# Power_Supply.net
KiCad netlist of a schematic drawn in Altium Designer
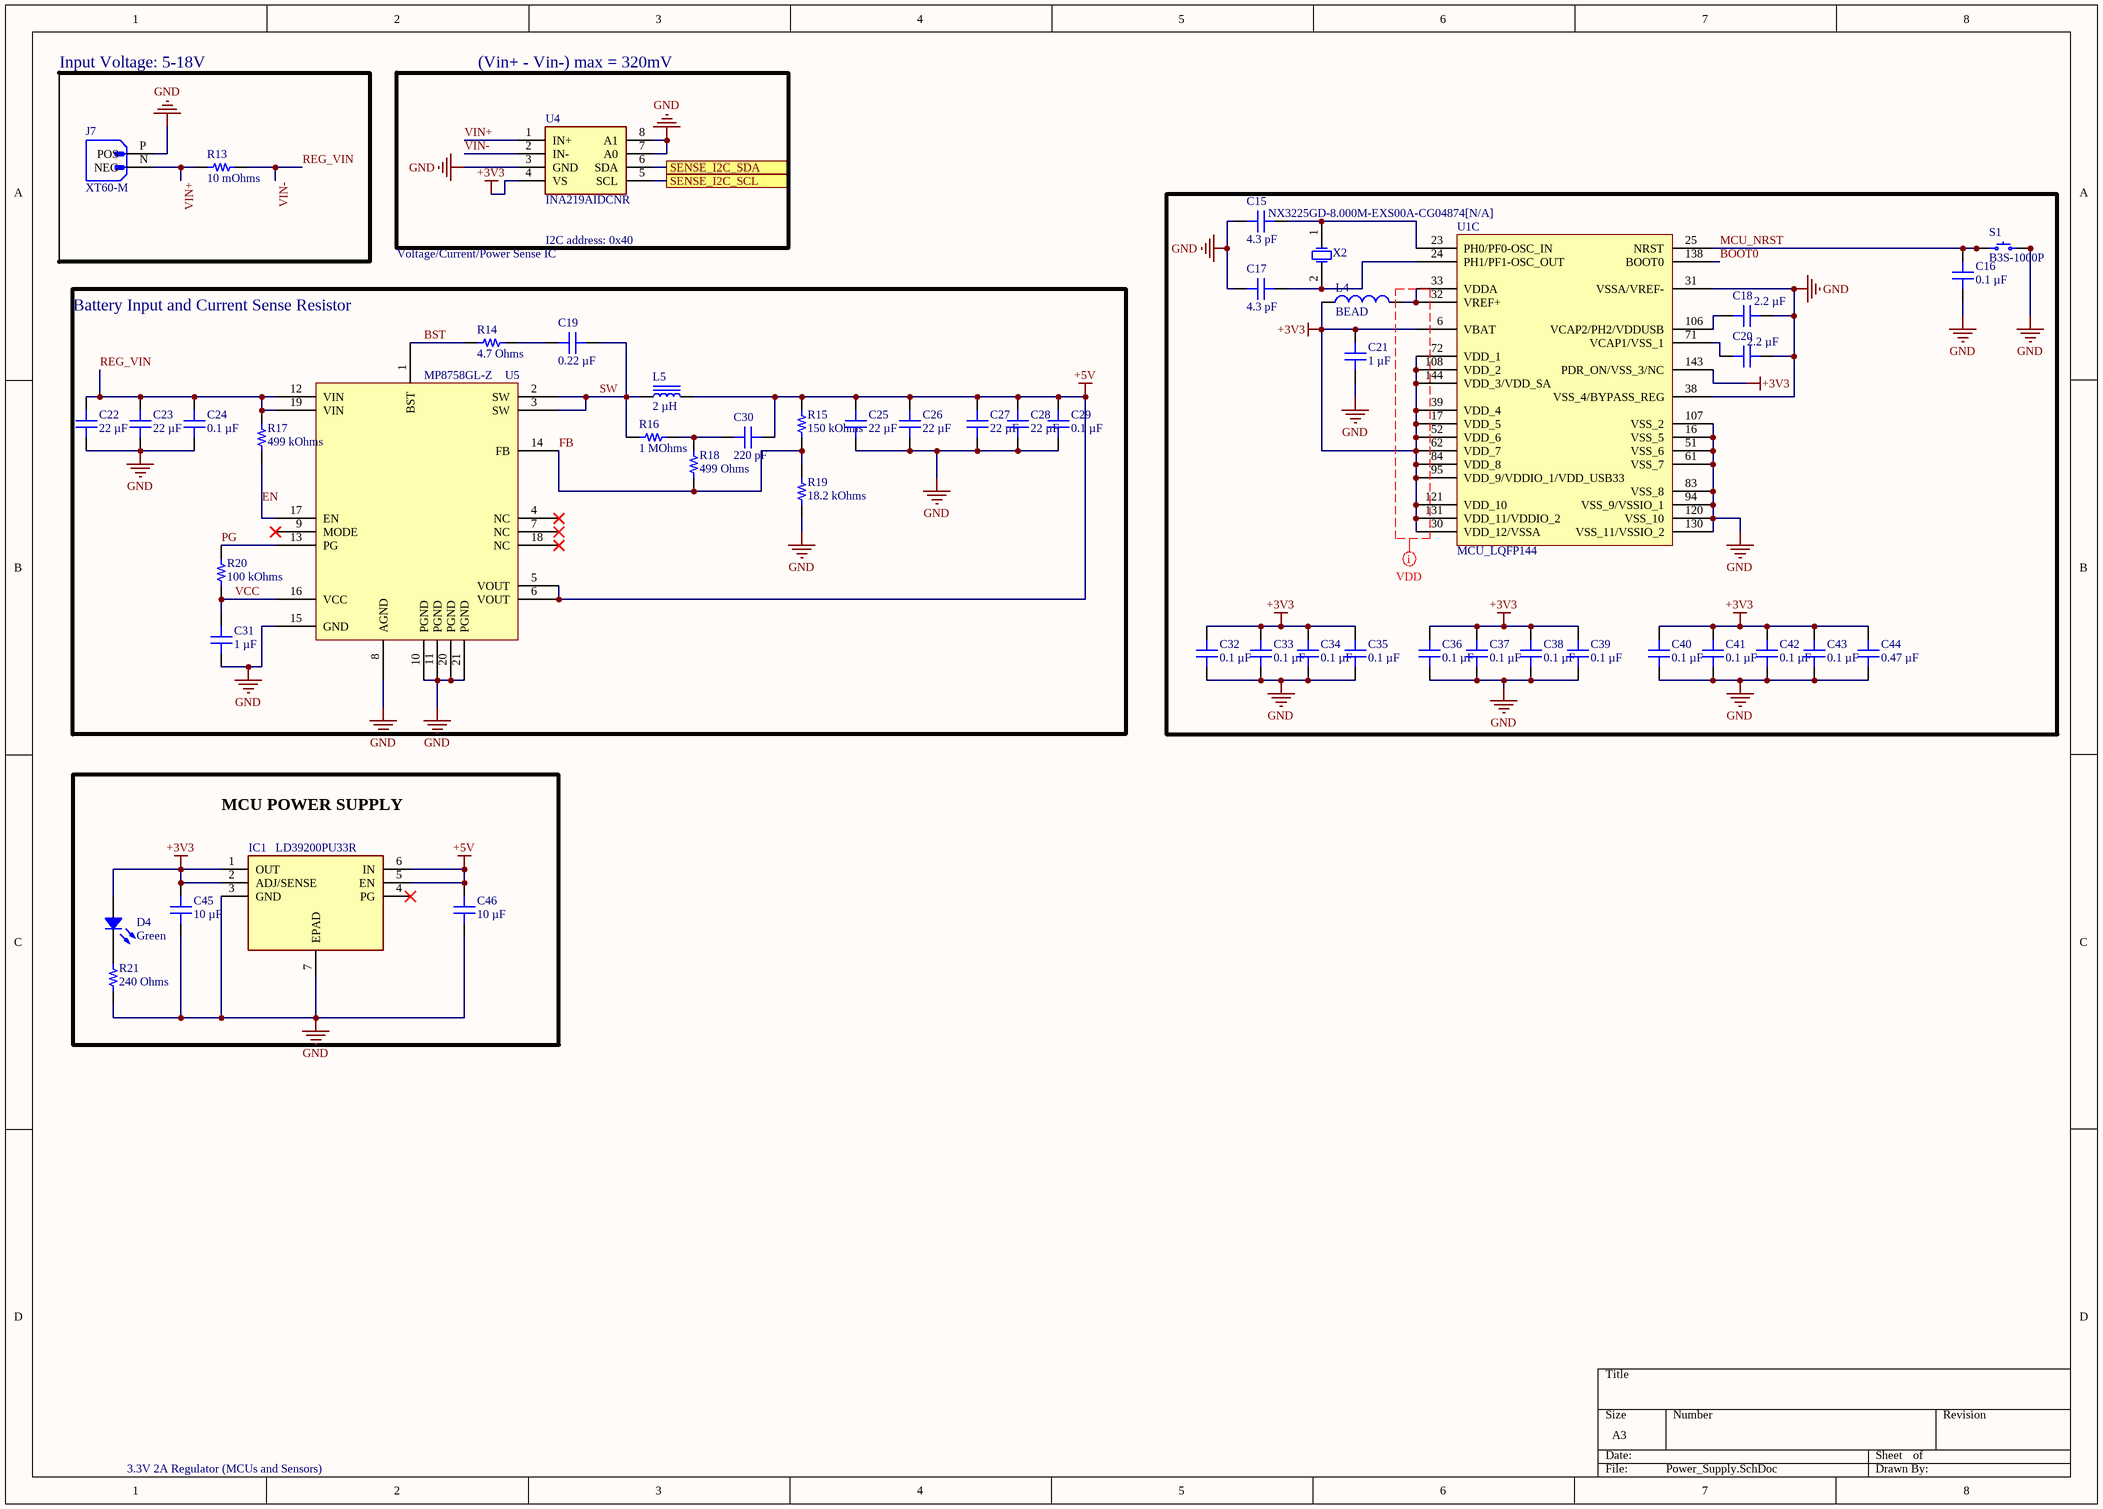
[diagram p0: Power_Supply.SchDoc]

(export (version "E")
  (design (tool "Eeschema 10.0.6"))
  (components
    (comp (ref "C15")
      (value "4.3 pF")
      (footprint "CAP 0603_1608")
      (description "CAP CER 4.3PF 50V C0G/NPO 0603")
      (fields (field (name "PART NUMBER") "CC0603CRNPO9BN4R3") (field (name "MANUFACTURER") "Yageo"))
      (libsource (lib "Celestial Altium Library - altium_library") (part "Capacitor"))
    )
    (comp (ref "C16")
      (value "0.1 µF")
      (footprint "CAP 0603_1608")
      (description "CAP CER 0.1UF 16V X7R 0603")
      (fields (field (name "PART NUMBER") "CC0603KRX7R7BB104") (field (name "MANUFACTURER") "Yageo"))
      (libsource (lib "Celestial Altium Library - altium_library") (part "Capacitor"))
    )
    (comp (ref "C17")
      (value "4.3 pF")
      (footprint "CAP 0603_1608")
      (description "CAP CER 4.3PF 50V C0G/NPO 0603")
      (fields (field (name "PART NUMBER") "CC0603CRNPO9BN4R3") (field (name "MANUFACTURER") "Yageo"))
      (libsource (lib "Celestial Altium Library - altium_library") (part "Capacitor"))
    )
    (comp (ref "C18")
      (value "2.2 µF")
      (footprint "CAP 1206_3216 - 0.8MM")
      (description "CAP CER 2.2UF 16V X7R 1206")
      (fields (field (name "PART NUMBER") "CC1206KKX7R7BB225") (field (name "MANUFACTURER") "Yageo"))
      (libsource (lib "Celestial Altium Library - altium_library") (part "Capacitor"))
    )
    (comp (ref "C19")
      (value "0.22 µF")
      (footprint "CAP 0603_1608")
      (description "CAP CER 0.22UF 25V X7R 0603")
      (fields
        (field (name "PART NUMBER") "CL10B224KA8NNNC")
        (field (name "MANUFACTURER") "Samsung Electro-Mechanics")
      )
      (libsource (lib "Celestial Altium Library - altium_library") (part "Capacitor"))
    )
    (comp (ref "C20")
      (value "2.2 µF")
      (footprint "CAP 1206_3216 - 0.8MM")
      (description "CAP CER 2.2UF 16V X7R 1206")
      (fields (field (name "PART NUMBER") "CC1206KKX7R7BB225") (field (name "MANUFACTURER") "Yageo"))
      (libsource (lib "Celestial Altium Library - altium_library") (part "Capacitor"))
    )
    (comp (ref "C21")
      (value "1 µF")
      (footprint "CAP 0603_1608")
      (description "CAP CER 1UF 16V X5R 0603")
      (fields
        (field (name "PART NUMBER") "CL10A105KO8NNNC")
        (field (name "MANUFACTURER") "Samsung Electro-Mechanics")
      )
      (libsource (lib "Celestial Altium Library - altium_library") (part "Capacitor"))
    )
    (comp (ref "C22")
      (value "22 µF")
      (footprint "CAP 1206_3216 - 0.8MM")
      (description "CAP CER 22UF 25V X5R 1206")
      (fields
        (field (name "PART NUMBER") "CL31A226KAHNNNE")
        (field (name "MANUFACTURER") "Samsung Electro-Mechanics")
      )
      (libsource (lib "Celestial Altium Library - altium_library") (part "Capacitor"))
    )
    (comp (ref "C23")
      (value "22 µF")
      (footprint "CAP 1206_3216 - 0.8MM")
      (description "CAP CER 22UF 25V X5R 1206")
      (fields
        (field (name "PART NUMBER") "CL31A226KAHNNNE")
        (field (name "MANUFACTURER") "Samsung Electro-Mechanics")
      )
      (libsource (lib "Celestial Altium Library - altium_library") (part "Capacitor"))
    )
    (comp (ref "C24")
      (value "0.1 µF")
      (footprint "CAP 0805_2012")
      (description "CAP CER 0.1UF 25V X7R 0603")
      (fields
        (field (name "PART NUMBER") "CL10B104KA8NNNC")
        (field (name "MANUFACTURER") "Samsung Electro-Mechanics")
      )
      (libsource (lib "Celestial Altium Library - altium_library") (part "Capacitor"))
    )
    (comp (ref "C25")
      (value "22 µF")
      (footprint "CAP 1206_3216 - 0.8MM")
      (description "CAP CER 22UF 16V X5R 1206")
      (fields (field (name "PART NUMBER") "EMK316BJ226ML-T") (field (name "MANUFACTURER") "Taiyo Yuden"))
      (libsource (lib "Celestial Altium Library - altium_library") (part "Capacitor"))
    )
    (comp (ref "C26")
      (value "22 µF")
      (footprint "CAP 1206_3216 - 0.8MM")
      (description "CAP CER 22UF 16V X5R 1206")
      (fields (field (name "PART NUMBER") "EMK316BJ226ML-T") (field (name "MANUFACTURER") "Taiyo Yuden"))
      (libsource (lib "Celestial Altium Library - altium_library") (part "Capacitor"))
    )
    (comp (ref "C27")
      (value "22 µF")
      (footprint "CAP 1206_3216 - 0.8MM")
      (description "CAP CER 22UF 16V X5R 1206")
      (fields (field (name "PART NUMBER") "EMK316BJ226ML-T") (field (name "MANUFACTURER") "Taiyo Yuden"))
      (libsource (lib "Celestial Altium Library - altium_library") (part "Capacitor"))
    )
    (comp (ref "C28")
      (value "22 µF")
      (footprint "CAP 1206_3216 - 0.8MM")
      (description "CAP CER 22UF 16V X5R 1206")
      (fields (field (name "PART NUMBER") "EMK316BJ226ML-T") (field (name "MANUFACTURER") "Taiyo Yuden"))
      (libsource (lib "Celestial Altium Library - altium_library") (part "Capacitor"))
    )
    (comp (ref "C29")
      (value "0.1 µF")
      (footprint "CAP 0603_1608")
      (description "CAP CER 0.1UF 25V X7R 0603")
      (fields
        (field (name "PART NUMBER") "CL10B104KA8NNNC")
        (field (name "MANUFACTURER") "Samsung Electro-Mechanics")
      )
      (libsource (lib "Celestial Altium Library - altium_library") (part "Capacitor"))
    )
    (comp (ref "C30")
      (value "220 pF")
      (footprint "CAP 0603_1608")
      (description "CAP CER 220PF 50V X7R 0603")
      (fields
        (field (name "PART NUMBER") "CL10B221KB8NNNC")
        (field (name "MANUFACTURER") "Samsung Electro-Mechanics")
      )
      (libsource (lib "Celestial Altium Library - altium_library") (part "Capacitor"))
    )
    (comp (ref "C31")
      (value "1 µF")
      (footprint "CAP 0603_1608")
      (description "CAP CER 1UF 25V X7R 0603")
      (fields
        (field (name "PART NUMBER") "CL10B105KA8NNNC")
        (field (name "MANUFACTURER") "Samsung Electro-Mechanics")
      )
      (libsource (lib "Celestial Altium Library - altium_library") (part "Capacitor"))
    )
    (comp (ref "C32")
      (value "0.1 µF")
      (footprint "CAP 0603_1608")
      (description "CAP CER 0.1UF 16V X7R 0603")
      (fields (field (name "PART NUMBER") "CC0603KRX7R7BB104") (field (name "MANUFACTURER") "Yageo"))
      (libsource (lib "Celestial Altium Library - altium_library") (part "Capacitor"))
    )
    (comp (ref "C33")
      (value "0.1 µF")
      (footprint "CAP 0603_1608")
      (description "CAP CER 0.1UF 16V X7R 0603")
      (fields (field (name "PART NUMBER") "CC0603KRX7R7BB104") (field (name "MANUFACTURER") "Yageo"))
      (libsource (lib "Celestial Altium Library - altium_library") (part "Capacitor"))
    )
    (comp (ref "C34")
      (value "0.1 µF")
      (footprint "CAP 0603_1608")
      (description "CAP CER 0.1UF 16V X7R 0603")
      (fields (field (name "PART NUMBER") "CC0603KRX7R7BB104") (field (name "MANUFACTURER") "Yageo"))
      (libsource (lib "Celestial Altium Library - altium_library") (part "Capacitor"))
    )
    (comp (ref "C35")
      (value "0.1 µF")
      (footprint "CAP 0603_1608")
      (description "CAP CER 0.1UF 16V X7R 0603")
      (fields (field (name "PART NUMBER") "CC0603KRX7R7BB104") (field (name "MANUFACTURER") "Yageo"))
      (libsource (lib "Celestial Altium Library - altium_library") (part "Capacitor"))
    )
    (comp (ref "C36")
      (value "0.1 µF")
      (footprint "CAP 0603_1608")
      (description "CAP CER 0.1UF 16V X7R 0603")
      (fields (field (name "PART NUMBER") "CC0603KRX7R7BB104") (field (name "MANUFACTURER") "Yageo"))
      (libsource (lib "Celestial Altium Library - altium_library") (part "Capacitor"))
    )
    (comp (ref "C37")
      (value "0.1 µF")
      (footprint "CAP 0603_1608")
      (description "CAP CER 0.1UF 16V X7R 0603")
      (fields (field (name "PART NUMBER") "CC0603KRX7R7BB104") (field (name "MANUFACTURER") "Yageo"))
      (libsource (lib "Celestial Altium Library - altium_library") (part "Capacitor"))
    )
    (comp (ref "C38")
      (value "0.1 µF")
      (footprint "CAP 0603_1608")
      (description "CAP CER 0.1UF 16V X7R 0603")
      (fields (field (name "PART NUMBER") "CC0603KRX7R7BB104") (field (name "MANUFACTURER") "Yageo"))
      (libsource (lib "Celestial Altium Library - altium_library") (part "Capacitor"))
    )
    (comp (ref "C39")
      (value "0.1 µF")
      (footprint "CAP 0603_1608")
      (description "CAP CER 0.1UF 16V X7R 0603")
      (fields (field (name "PART NUMBER") "CC0603KRX7R7BB104") (field (name "MANUFACTURER") "Yageo"))
      (libsource (lib "Celestial Altium Library - altium_library") (part "Capacitor"))
    )
    (comp (ref "C40")
      (value "0.1 µF")
      (footprint "CAP 0603_1608")
      (description "CAP CER 0.1UF 16V X7R 0603")
      (fields (field (name "PART NUMBER") "CC0603KRX7R7BB104") (field (name "MANUFACTURER") "Yageo"))
      (libsource (lib "Celestial Altium Library - altium_library") (part "Capacitor"))
    )
    (comp (ref "C41")
      (value "0.1 µF")
      (footprint "CAP 0603_1608")
      (description "CAP CER 0.1UF 16V X7R 0603")
      (fields (field (name "PART NUMBER") "CC0603KRX7R7BB104") (field (name "MANUFACTURER") "Yageo"))
      (libsource (lib "Celestial Altium Library - altium_library") (part "Capacitor"))
    )
    (comp (ref "C42")
      (value "0.1 µF")
      (footprint "CAP 0603_1608")
      (description "CAP CER 0.1UF 16V X7R 0603")
      (fields (field (name "PART NUMBER") "CC0603KRX7R7BB104") (field (name "MANUFACTURER") "Yageo"))
      (libsource (lib "Celestial Altium Library - altium_library") (part "Capacitor"))
    )
    (comp (ref "C43")
      (value "0.1 µF")
      (footprint "CAP 0603_1608")
      (description "CAP CER 0.1UF 16V X7R 0603")
      (fields (field (name "PART NUMBER") "CC0603KRX7R7BB104") (field (name "MANUFACTURER") "Yageo"))
      (libsource (lib "Celestial Altium Library - altium_library") (part "Capacitor"))
    )
    (comp (ref "C44")
      (value "0.47 µF")
      (footprint "CAP 1206_3216 - 1.8MM")
      (description "CAP CER 0.47UF 16V X7R 0603")
      (fields (field (name "PART NUMBER") "CC0603KRX7R7BB474") (field (name "MANUFACTURER") "Yageo"))
      (libsource (lib "Celestial Altium Library - altium_library") (part "Capacitor"))
    )
    (comp (ref "C45")
      (value "10 µF")
      (footprint "CAP 1206_3216 - 1.8MM")
      (description "CAP CER 10UF 16V X5R 0603")
      (fields
        (field (name "PART NUMBER") "GRM188R61C106MA73D")
        (field (name "MANUFACTURER") "Murata Electronics")
      )
      (libsource (lib "Celestial Altium Library - altium_library") (part "Capacitor"))
    )
    (comp (ref "C46")
      (value "10 µF")
      (footprint "CAP 0603_1608")
      (description "CAP CER 10UF 16V X5R 0603")
      (fields
        (field (name "PART NUMBER") "GRM188R61C106MA73D")
        (field (name "MANUFACTURER") "Murata Electronics")
      )
      (libsource (lib "Celestial Altium Library - altium_library") (part "Capacitor"))
    )
    (comp (ref "D4")
      (value "Green")
      (footprint "LED 0603_1608 GREEN")
      (description "LED GREEN CLEAR CHIP SMD")
      (fields (field (name "PART NUMBER") "LTST-C190KGKT") (field (name "MANUFACTURER") "Lite-On Inc."))
      (libsource (lib "Celestial Altium Library - altium_library") (part "LED"))
    )
    (comp (ref "IC1")
      (value "LD39200PU33R")
      (footprint "SamacSys:SON95P300X300X100-7N-D")
      (description "Integrated Circuit")
      (fields (field (name "MOUSER PART NUMBER") "511-LD39200PU33R"))
      (libsource (lib "*") (part "LD39200PU33R"))
    )
    (comp (ref "J7")
      (value "XT60-M")
      (footprint "AMASS_XT60-M")
      (description "Plug; DC supply; XT60; male; PIN: 2; for cable; soldered; 30A; 500V")
      (fields (field (name "MF") "AMASS"))
      (libsource (lib "Flight_controller v1.0") (part "XT60-M"))
    )
    (comp (ref "L4")
      (value "BEAD")
      (footprint "IND_FCM1608_TTC")
      (description "Inductor")
      (fields (field (name "PUBLISHER") "Altium Limited"))
      (libsource (lib "Flight_controller v1.0") (part "Inductor_1"))
    )
    (comp (ref "L5")
      (value "2 µH")
      (footprint "WURTH WE-HCI 1365")
      (description "FIXED IND 2UH 23A 2.6 MOHM SMD")
      (fields (field (name "PART NUMBER") "7443551200") (field (name "MANUFACTURER") "Würth Elektronik"))
      (libsource (lib "Celestial Altium Library - altium_library") (part "Inductor"))
    )
    (comp (ref "R13")
      (value "10 mOhms")
      (footprint "RES 2512_6432")
      (description "RES 0.01 OHM 0.5% 1W 2512")
      (fields
        (field (name "PART NUMBER") "Y14870R01000D5W")
        (field (name "MANUFACTURER") "Vishay Foil Resistors (Division of Vishay Precision Group)")
      )
      (libsource (lib "Celestial Altium Library - altium_library") (part "Resistor"))
    )
    (comp (ref "R14")
      (value "4.7 Ohms")
      (footprint "RES 0603_1608")
      (description "RES SMD 4.7 OHM 5% 1/10W 0603")
      (fields
        (field (name "PART NUMBER") "ERJ-3GEYJ4R7V")
        (field (name "MANUFACTURER") "Panasonic Electronic Components")
      )
      (libsource (lib "Celestial Altium Library - altium_library") (part "Resistor"))
    )
    (comp (ref "R15")
      (value "150 kOhms")
      (footprint "RES 0805_2012")
      (description "RES 150K OHM 1% 1/10W 0603")
      (fields (field (name "PART NUMBER") "RC0603FR-07150KL") (field (name "MANUFACTURER") "Yageo"))
      (libsource (lib "Celestial Altium Library - altium_library") (part "Resistor"))
    )
    (comp (ref "R16")
      (value "1 MOhms")
      (footprint "RES 0603_1608")
      (description "RES SMD 1M OHM 0.1% 1/10W 0603")
      (fields (field (name "PART NUMBER") "RT0603BRD071ML") (field (name "MANUFACTURER") "Yageo"))
      (libsource (lib "Celestial Altium Library - altium_library") (part "Resistor"))
    )
    (comp (ref "R17")
      (value "499 kOhms")
      (footprint "RES 0805_2012")
      (description "RES 499K OHM 1% 1/10W 0603")
      (fields (field (name "PART NUMBER") "RC0603FR-07499KL") (field (name "MANUFACTURER") "Yageo"))
      (libsource (lib "Celestial Altium Library - altium_library") (part "Resistor"))
    )
    (comp (ref "R18")
      (value "499 Ohms")
      (footprint "RES 0603_1608")
      (description "RES 499 OHM 1% 1/10W 0603")
      (fields (field (name "PART NUMBER") "RC0603FR-07499RL") (field (name "MANUFACTURER") "Yageo"))
      (libsource (lib "Celestial Altium Library - altium_library") (part "Resistor"))
    )
    (comp (ref "R19")
      (value "18.2 kOhms")
      (footprint "RES 0805_2012")
      (description "RES 18.2K OHM 1% 1/10W 0603")
      (fields (field (name "PART NUMBER") "RC0603FR-0718K2L") (field (name "MANUFACTURER") "Yageo"))
      (libsource (lib "Celestial Altium Library - altium_library") (part "Resistor"))
    )
    (comp (ref "R20")
      (value "100 kOhms")
      (footprint "RES 0603_1608")
      (description "RES 100K OHM 1% 1/10W 0603")
      (fields (field (name "PART NUMBER") "RC0603FR-07100KL") (field (name "MANUFACTURER") "Yageo"))
      (libsource (lib "Celestial Altium Library - altium_library") (part "Resistor"))
    )
    (comp (ref "R21")
      (value "240 Ohms")
      (footprint "RES 0603_1608")
      (description "RES 240 OHM 1% 1/10W 0603")
      (fields (field (name "PART NUMBER") "RC0603FR-07240RL") (field (name "MANUFACTURER") "Yageo"))
      (libsource (lib "Celestial Altium Library - altium_library") (part "Resistor"))
    )
    (comp (ref "S1")
      (value "B3S-1000P")
      (footprint "OMRON B3S-1000P")
      (description "SWITCH TACTILE SPST-NO 0.05A 24V")
      (fields (field (name "MANUFACTURER") "Omron Electronics Inc-EMC Div"))
      (libsource (lib "Celestial Altium Library - altium_library") (part "SPST-NO 4 PIN"))
    )
    (comp (ref "U1")
      (value "MCU_LQFP144")
      (footprint "LQFP144-20x20mm")
      (libsource (lib "Flight_controller v1.0") (part "MCU_LQFP144"))
    )
    (comp (ref "U4")
      (value "INA219AIDCNR")
      (footprint "SamacSys:SOP65P280X145-8N")
      (description "Integrated Circuit")
      (fields (field (name "MOUSER PART NUMBER") "595-INA219AIDCNR"))
      (libsource (lib "Flight_controller v1.0") (part "INA219AIDCNR"))
    )
    (comp (ref "U5")
      (value "MP8758GL-Z")
      (footprint "MP8758HGL-Z")
      (description "No Description Available")
      (fields (field (name "COPYRIGHT") "Copyright (C) 2023 Ultra Librarian. All rights reserved."))
      (libsource (lib "Flight_controller v1.0") (part "MP8758GL-Z"))
    )
    (comp (ref "X2")
      (value "NX3225GD-8.000M-EXS00A-CG04874[N/A]")
      (footprint "XTAL_NX3225GD_NDK")
      (description "Crystal Oscillator")
      (fields (field (name "PUBLISHER") "Altium Limited"))
      (libsource (lib "Flight_controller v1.0") (part "XTAL"))
    )
  )
  (nets
    (net (code "1") (name "+3V3") (class "Default")
      (node (ref "C21") (pin "2") (pinfunction "2_2") (pintype "passive"))
      (node (ref "C32") (pin "2") (pinfunction "2_2") (pintype "passive"))
      (node (ref "C33") (pin "2") (pinfunction "2_2") (pintype "passive"))
      (node (ref "C34") (pin "2") (pinfunction "2_2") (pintype "passive"))
      (node (ref "C35") (pin "2") (pinfunction "2_2") (pintype "passive"))
      (node (ref "C36") (pin "2") (pinfunction "2_2") (pintype "passive"))
      (node (ref "C37") (pin "2") (pinfunction "2_2") (pintype "passive"))
      (node (ref "C38") (pin "2") (pinfunction "2_2") (pintype "passive"))
      (node (ref "C39") (pin "2") (pinfunction "2_2") (pintype "passive"))
      (node (ref "C40") (pin "2") (pinfunction "2_2") (pintype "passive"))
      (node (ref "C41") (pin "2") (pinfunction "2_2") (pintype "passive"))
      (node (ref "C42") (pin "2") (pinfunction "2_2") (pintype "passive"))
      (node (ref "C43") (pin "2") (pinfunction "2_2") (pintype "passive"))
      (node (ref "C44") (pin "2") (pinfunction "2_2") (pintype "passive"))
      (node (ref "C45") (pin "2") (pinfunction "2_2") (pintype "passive"))
      (node (ref "D4") (pin "1") (pinfunction "1_1") (pintype "passive"))
      (node (ref "IC1") (pin "1") (pinfunction "OUT_1") (pintype "passive"))
      (node (ref "IC1") (pin "2") (pinfunction "ADJ/SENSE_2") (pintype "passive"))
      (node (ref "L4") (pin "1") (pinfunction "1_1") (pintype "passive"))
      (node (ref "U1") (pin "108") (pinfunction "VDD_2_108") (pintype "passive"))
      (node (ref "U1") (pin "121") (pinfunction "VDD_10_121") (pintype "passive"))
      (node (ref "U1") (pin "131") (pinfunction "VDD_11/VDDIO_2_131") (pintype "passive"))
      (node (ref "U1") (pin "143") (pinfunction "PDR_ON/VSS_3/NC_143") (pintype "passive"))
      (node (ref "U1") (pin "144") (pinfunction "VDD_3/VDD_SA_144") (pintype "passive"))
      (node (ref "U1") (pin "17") (pinfunction "VDD_5_17") (pintype "passive"))
      (node (ref "U1") (pin "30") (pinfunction "VDD_12/VSSA_30") (pintype "passive"))
      (node (ref "U1") (pin "39") (pinfunction "VDD_4_39") (pintype "passive"))
      (node (ref "U1") (pin "52") (pinfunction "VDD_6_52") (pintype "passive"))
      (node (ref "U1") (pin "6") (pinfunction "VBAT_6") (pintype "passive"))
      (node (ref "U1") (pin "62") (pinfunction "VDD_7_62") (pintype "passive"))
      (node (ref "U1") (pin "72") (pinfunction "VDD_1_72") (pintype "passive"))
      (node (ref "U1") (pin "84") (pinfunction "VDD_8_84") (pintype "passive"))
      (node (ref "U1") (pin "95") (pinfunction "VDD_9/VDDIO_1/VDD_USB33_95") (pintype "passive"))
      (node (ref "U4") (pin "4") (pinfunction "VS_4") (pintype "passive"))
    )
    (net (code "2") (name "+5V") (class "Default")
      (node (ref "C25") (pin "2") (pinfunction "2_2") (pintype "passive"))
      (node (ref "C26") (pin "2") (pinfunction "2_2") (pintype "passive"))
      (node (ref "C27") (pin "2") (pinfunction "2_2") (pintype "passive"))
      (node (ref "C28") (pin "2") (pinfunction "2_2") (pintype "passive"))
      (node (ref "C29") (pin "2") (pinfunction "2_2") (pintype "passive"))
      (node (ref "C30") (pin "2") (pinfunction "2_2") (pintype "passive"))
      (node (ref "C46") (pin "2") (pinfunction "2_2") (pintype "passive"))
      (node (ref "IC1") (pin "5") (pinfunction "EN_5") (pintype "passive"))
      (node (ref "IC1") (pin "6") (pinfunction "IN_6") (pintype "passive"))
      (node (ref "L5") (pin "2") (pinfunction "2_2") (pintype "passive"))
      (node (ref "R15") (pin "2") (pinfunction "2_2") (pintype "passive"))
      (node (ref "U5") (pin "5") (pinfunction "VOUT_5") (pintype "passive"))
      (node (ref "U5") (pin "6") (pinfunction "VOUT_6") (pintype "passive"))
    )
    (net (code "3") (name "/BOOT0") (class "Default")
      (node (ref "U1") (pin "138") (pinfunction "BOOT0_138") (pintype "passive"))
    )
    (net (code "4") (name "/BST") (class "Default")
      (node (ref "R14") (pin "1") (pinfunction "1_1") (pintype "passive"))
      (node (ref "U5") (pin "1") (pinfunction "BST_1") (pintype "passive"))
    )
    (net (code "5") (name "/EN") (class "Default")
      (node (ref "R17") (pin "1") (pinfunction "1_1") (pintype "passive"))
      (node (ref "U5") (pin "17") (pinfunction "EN_17") (pintype "passive"))
    )
    (net (code "6") (name "/FB") (class "Default")
      (node (ref "R15") (pin "1") (pinfunction "1_1") (pintype "passive"))
      (node (ref "R18") (pin "1") (pinfunction "1_1") (pintype "passive"))
      (node (ref "R19") (pin "2") (pinfunction "2_2") (pintype "passive"))
      (node (ref "U5") (pin "14") (pinfunction "FB_14") (pintype "passive"))
    )
    (net (code "7") (name "/MCU_NRST") (class "Default")
      (node (ref "C16") (pin "2") (pinfunction "2_2") (pintype "passive"))
      (node (ref "S1") (pin "1") (pinfunction "1_1") (pintype "passive"))
      (node (ref "S1") (pin "2") (pinfunction "2_2") (pintype "passive"))
      (node (ref "U1") (pin "25") (pinfunction "NRST_25") (pintype "passive"))
    )
    (net (code "8") (name "/PG") (class "Default")
      (node (ref "R20") (pin "2") (pinfunction "2_2") (pintype "passive"))
      (node (ref "U5") (pin "13") (pinfunction "PG_13") (pintype "passive"))
    )
    (net (code "9") (name "/REG_VIN") (class "Default")
      (node (ref "C22") (pin "2") (pinfunction "2_2") (pintype "passive"))
      (node (ref "C23") (pin "2") (pinfunction "2_2") (pintype "passive"))
      (node (ref "C24") (pin "2") (pinfunction "2_2") (pintype "passive"))
      (node (ref "R13") (pin "2") (pinfunction "2_2") (pintype "passive"))
      (node (ref "R17") (pin "2") (pinfunction "2_2") (pintype "passive"))
      (node (ref "U4") (pin "2") (pinfunction "IN-_2") (pintype "passive"))
      (node (ref "U5") (pin "12") (pinfunction "VIN_12") (pintype "passive"))
      (node (ref "U5") (pin "19") (pinfunction "VIN_19") (pintype "passive"))
    )
    (net (code "10") (name "/SENSE_I2C_SCL") (class "Default")
      (node (ref "U4") (pin "5") (pinfunction "SCL_5") (pintype "passive"))
    )
    (net (code "11") (name "/SENSE_I2C_SDA") (class "Default")
      (node (ref "U4") (pin "6") (pinfunction "SDA_6") (pintype "passive"))
    )
    (net (code "12") (name "/SW") (class "Default")
      (node (ref "C19") (pin "2") (pinfunction "2_2") (pintype "passive"))
      (node (ref "L5") (pin "1") (pinfunction "1_1") (pintype "passive"))
      (node (ref "R16") (pin "2") (pinfunction "2_2") (pintype "passive"))
      (node (ref "U5") (pin "2") (pinfunction "SW_2") (pintype "passive"))
      (node (ref "U5") (pin "3") (pinfunction "SW_3") (pintype "passive"))
    )
    (net (code "13") (name "/VCC") (class "Default")
      (node (ref "C31") (pin "2") (pinfunction "2_2") (pintype "passive"))
      (node (ref "R20") (pin "1") (pinfunction "1_1") (pintype "passive"))
      (node (ref "U5") (pin "16") (pinfunction "VCC_16") (pintype "passive"))
    )
    (net (code "14") (name "/VIN+") (class "Default")
      (node (ref "J7") (pin "N") (pinfunction "NEG_N") (pintype "passive"))
      (node (ref "R13") (pin "1") (pinfunction "1_1") (pintype "passive"))
      (node (ref "U4") (pin "1") (pinfunction "IN+_1") (pintype "passive"))
    )
    (net (code "15") (name "GND") (class "Default")
      (node (ref "C15") (pin "1") (pinfunction "1_1") (pintype "passive"))
      (node (ref "C16") (pin "1") (pinfunction "1_1") (pintype "passive"))
      (node (ref "C17") (pin "1") (pinfunction "1_1") (pintype "passive"))
      (node (ref "C18") (pin "2") (pinfunction "2_2") (pintype "passive"))
      (node (ref "C20") (pin "2") (pinfunction "2_2") (pintype "passive"))
      (node (ref "C21") (pin "1") (pinfunction "1_1") (pintype "passive"))
      (node (ref "C22") (pin "1") (pinfunction "1_1") (pintype "passive"))
      (node (ref "C23") (pin "1") (pinfunction "1_1") (pintype "passive"))
      (node (ref "C24") (pin "1") (pinfunction "1_1") (pintype "passive"))
      (node (ref "C25") (pin "1") (pinfunction "1_1") (pintype "passive"))
      (node (ref "C26") (pin "1") (pinfunction "1_1") (pintype "passive"))
      (node (ref "C27") (pin "1") (pinfunction "1_1") (pintype "passive"))
      (node (ref "C28") (pin "1") (pinfunction "1_1") (pintype "passive"))
      (node (ref "C29") (pin "1") (pinfunction "1_1") (pintype "passive"))
      (node (ref "C31") (pin "1") (pinfunction "1_1") (pintype "passive"))
      (node (ref "C32") (pin "1") (pinfunction "1_1") (pintype "passive"))
      (node (ref "C33") (pin "1") (pinfunction "1_1") (pintype "passive"))
      (node (ref "C34") (pin "1") (pinfunction "1_1") (pintype "passive"))
      (node (ref "C35") (pin "1") (pinfunction "1_1") (pintype "passive"))
      (node (ref "C36") (pin "1") (pinfunction "1_1") (pintype "passive"))
      (node (ref "C37") (pin "1") (pinfunction "1_1") (pintype "passive"))
      (node (ref "C38") (pin "1") (pinfunction "1_1") (pintype "passive"))
      (node (ref "C39") (pin "1") (pinfunction "1_1") (pintype "passive"))
      (node (ref "C40") (pin "1") (pinfunction "1_1") (pintype "passive"))
      (node (ref "C41") (pin "1") (pinfunction "1_1") (pintype "passive"))
      (node (ref "C42") (pin "1") (pinfunction "1_1") (pintype "passive"))
      (node (ref "C43") (pin "1") (pinfunction "1_1") (pintype "passive"))
      (node (ref "C44") (pin "1") (pinfunction "1_1") (pintype "passive"))
      (node (ref "C45") (pin "1") (pinfunction "1_1") (pintype "passive"))
      (node (ref "C46") (pin "1") (pinfunction "1_1") (pintype "passive"))
      (node (ref "IC1") (pin "3") (pinfunction "GND_3") (pintype "passive"))
      (node (ref "IC1") (pin "7") (pinfunction "EPAD_7") (pintype "passive"))
      (node (ref "J7") (pin "P") (pinfunction "POS_P") (pintype "passive"))
      (node (ref "R19") (pin "1") (pinfunction "1_1") (pintype "passive"))
      (node (ref "R21") (pin "1") (pinfunction "1_1") (pintype "passive"))
      (node (ref "S1") (pin "3") (pinfunction "3_3") (pintype "passive"))
      (node (ref "S1") (pin "4") (pinfunction "4_4") (pintype "passive"))
      (node (ref "U1") (pin "107") (pinfunction "VSS_2_107") (pintype "passive"))
      (node (ref "U1") (pin "120") (pinfunction "VSS_10_120") (pintype "passive"))
      (node (ref "U1") (pin "130") (pinfunction "VSS_11/VSSIO_2_130") (pintype "passive"))
      (node (ref "U1") (pin "16") (pinfunction "VSS_5_16") (pintype "passive"))
      (node (ref "U1") (pin "31") (pinfunction "VSSA/VREF-_31") (pintype "passive"))
      (node (ref "U1") (pin "38") (pinfunction "VSS_4/BYPASS_REG_38") (pintype "passive"))
      (node (ref "U1") (pin "51") (pinfunction "VSS_6_51") (pintype "passive"))
      (node (ref "U1") (pin "61") (pinfunction "VSS_7_61") (pintype "passive"))
      (node (ref "U1") (pin "83") (pinfunction "VSS_8_83") (pintype "passive"))
      (node (ref "U1") (pin "94") (pinfunction "VSS_9/VSSIO_1_94") (pintype "passive"))
      (node (ref "U4") (pin "3") (pinfunction "GND_3") (pintype "passive"))
      (node (ref "U4") (pin "7") (pinfunction "A0_7") (pintype "passive"))
      (node (ref "U4") (pin "8") (pinfunction "A1_8") (pintype "passive"))
      (node (ref "U5") (pin "10") (pinfunction "PGND_10") (pintype "passive"))
      (node (ref "U5") (pin "11") (pinfunction "PGND_11") (pintype "passive"))
      (node (ref "U5") (pin "15") (pinfunction "GND_15") (pintype "passive"))
      (node (ref "U5") (pin "20") (pinfunction "PGND_20") (pintype "passive"))
      (node (ref "U5") (pin "21") (pinfunction "PGND_21") (pintype "passive"))
      (node (ref "U5") (pin "8") (pinfunction "AGND_8") (pintype "passive"))
    )
    (net (code "16") (name "Net-(C19-Pad1)") (class "Default")
      (node (ref "C19") (pin "1") (pinfunction "1_1") (pintype "passive"))
      (node (ref "R14") (pin "2") (pinfunction "2_2") (pintype "passive"))
    )
    (net (code "17") (name "Net-(C30-Pad1)") (class "Default")
      (node (ref "C30") (pin "1") (pinfunction "1_1") (pintype "passive"))
      (node (ref "R16") (pin "1") (pinfunction "1_1") (pintype "passive"))
      (node (ref "R18") (pin "2") (pinfunction "2_2") (pintype "passive"))
    )
    (net (code "18") (name "Net-(D4-Pad2)") (class "Default")
      (node (ref "D4") (pin "2") (pinfunction "2_2") (pintype "passive"))
      (node (ref "R21") (pin "2") (pinfunction "2_2") (pintype "passive"))
    )
    (net (code "19") (name "Net-(U1C-PH0{slash}PF0-OSC_IN)") (class "Default")
      (node (ref "C15") (pin "2") (pinfunction "2_2") (pintype "passive"))
      (node (ref "U1") (pin "23") (pinfunction "PH0/PF0-OSC_IN_23") (pintype "passive"))
      (node (ref "X2") (pin "1") (pinfunction "OSC1_1") (pintype "passive"))
    )
    (net (code "20") (name "Net-(U1C-PH1{slash}PF1-OSC_OUT)") (class "Default")
      (node (ref "C17") (pin "2") (pinfunction "2_2") (pintype "passive"))
      (node (ref "U1") (pin "24") (pinfunction "PH1/PF1-OSC_OUT_24") (pintype "passive"))
      (node (ref "X2") (pin "2") (pinfunction "OSC2_2") (pintype "passive"))
    )
    (net (code "21") (name "Net-(U1C-VCAP1{slash}VSS_1)") (class "Default")
      (node (ref "C20") (pin "1") (pinfunction "1_1") (pintype "passive"))
      (node (ref "U1") (pin "71") (pinfunction "VCAP1/VSS_1_71") (pintype "passive"))
    )
    (net (code "22") (name "Net-(U1C-VCAP2{slash}PH2{slash}VDDUSB)") (class "Default")
      (node (ref "C18") (pin "1") (pinfunction "1_1") (pintype "passive"))
      (node (ref "U1") (pin "106") (pinfunction "VCAP2/PH2/VDDUSB_106") (pintype "passive"))
    )
    (net (code "23") (name "Net-(U1C-VDDA)") (class "Default")
      (node (ref "L4") (pin "2") (pinfunction "2_2") (pintype "passive"))
      (node (ref "U1") (pin "32") (pinfunction "VREF+_32") (pintype "passive"))
      (node (ref "U1") (pin "33") (pinfunction "VDDA_33") (pintype "passive"))
    )
    (net (code "24") (name "unconnected-(IC1-PG-Pad4)") (class "Default")
      (node (ref "IC1") (pin "4") (pinfunction "PG_4") (pintype "passive+no_connect"))
    )
    (net (code "25") (name "unconnected-(U5-MODE-Pad9)") (class "Default")
      (node (ref "U5") (pin "9") (pinfunction "MODE_9") (pintype "passive+no_connect"))
    )
    (net (code "26") (name "unconnected-(U5-NC-Pad4)") (class "Default")
      (node (ref "U5") (pin "4") (pinfunction "NC_4") (pintype "passive+no_connect"))
    )
    (net (code "27") (name "unconnected-(U5-NC-Pad7)") (class "Default")
      (node (ref "U5") (pin "7") (pinfunction "NC_7") (pintype "passive+no_connect"))
    )
    (net (code "28") (name "unconnected-(U5-NC-Pad18)") (class "Default")
      (node (ref "U5") (pin "18") (pinfunction "NC_18") (pintype "passive+no_connect"))
    )
  )
)
